# aiie.net
KiCad netlist of a schematic drawn in EAGLE
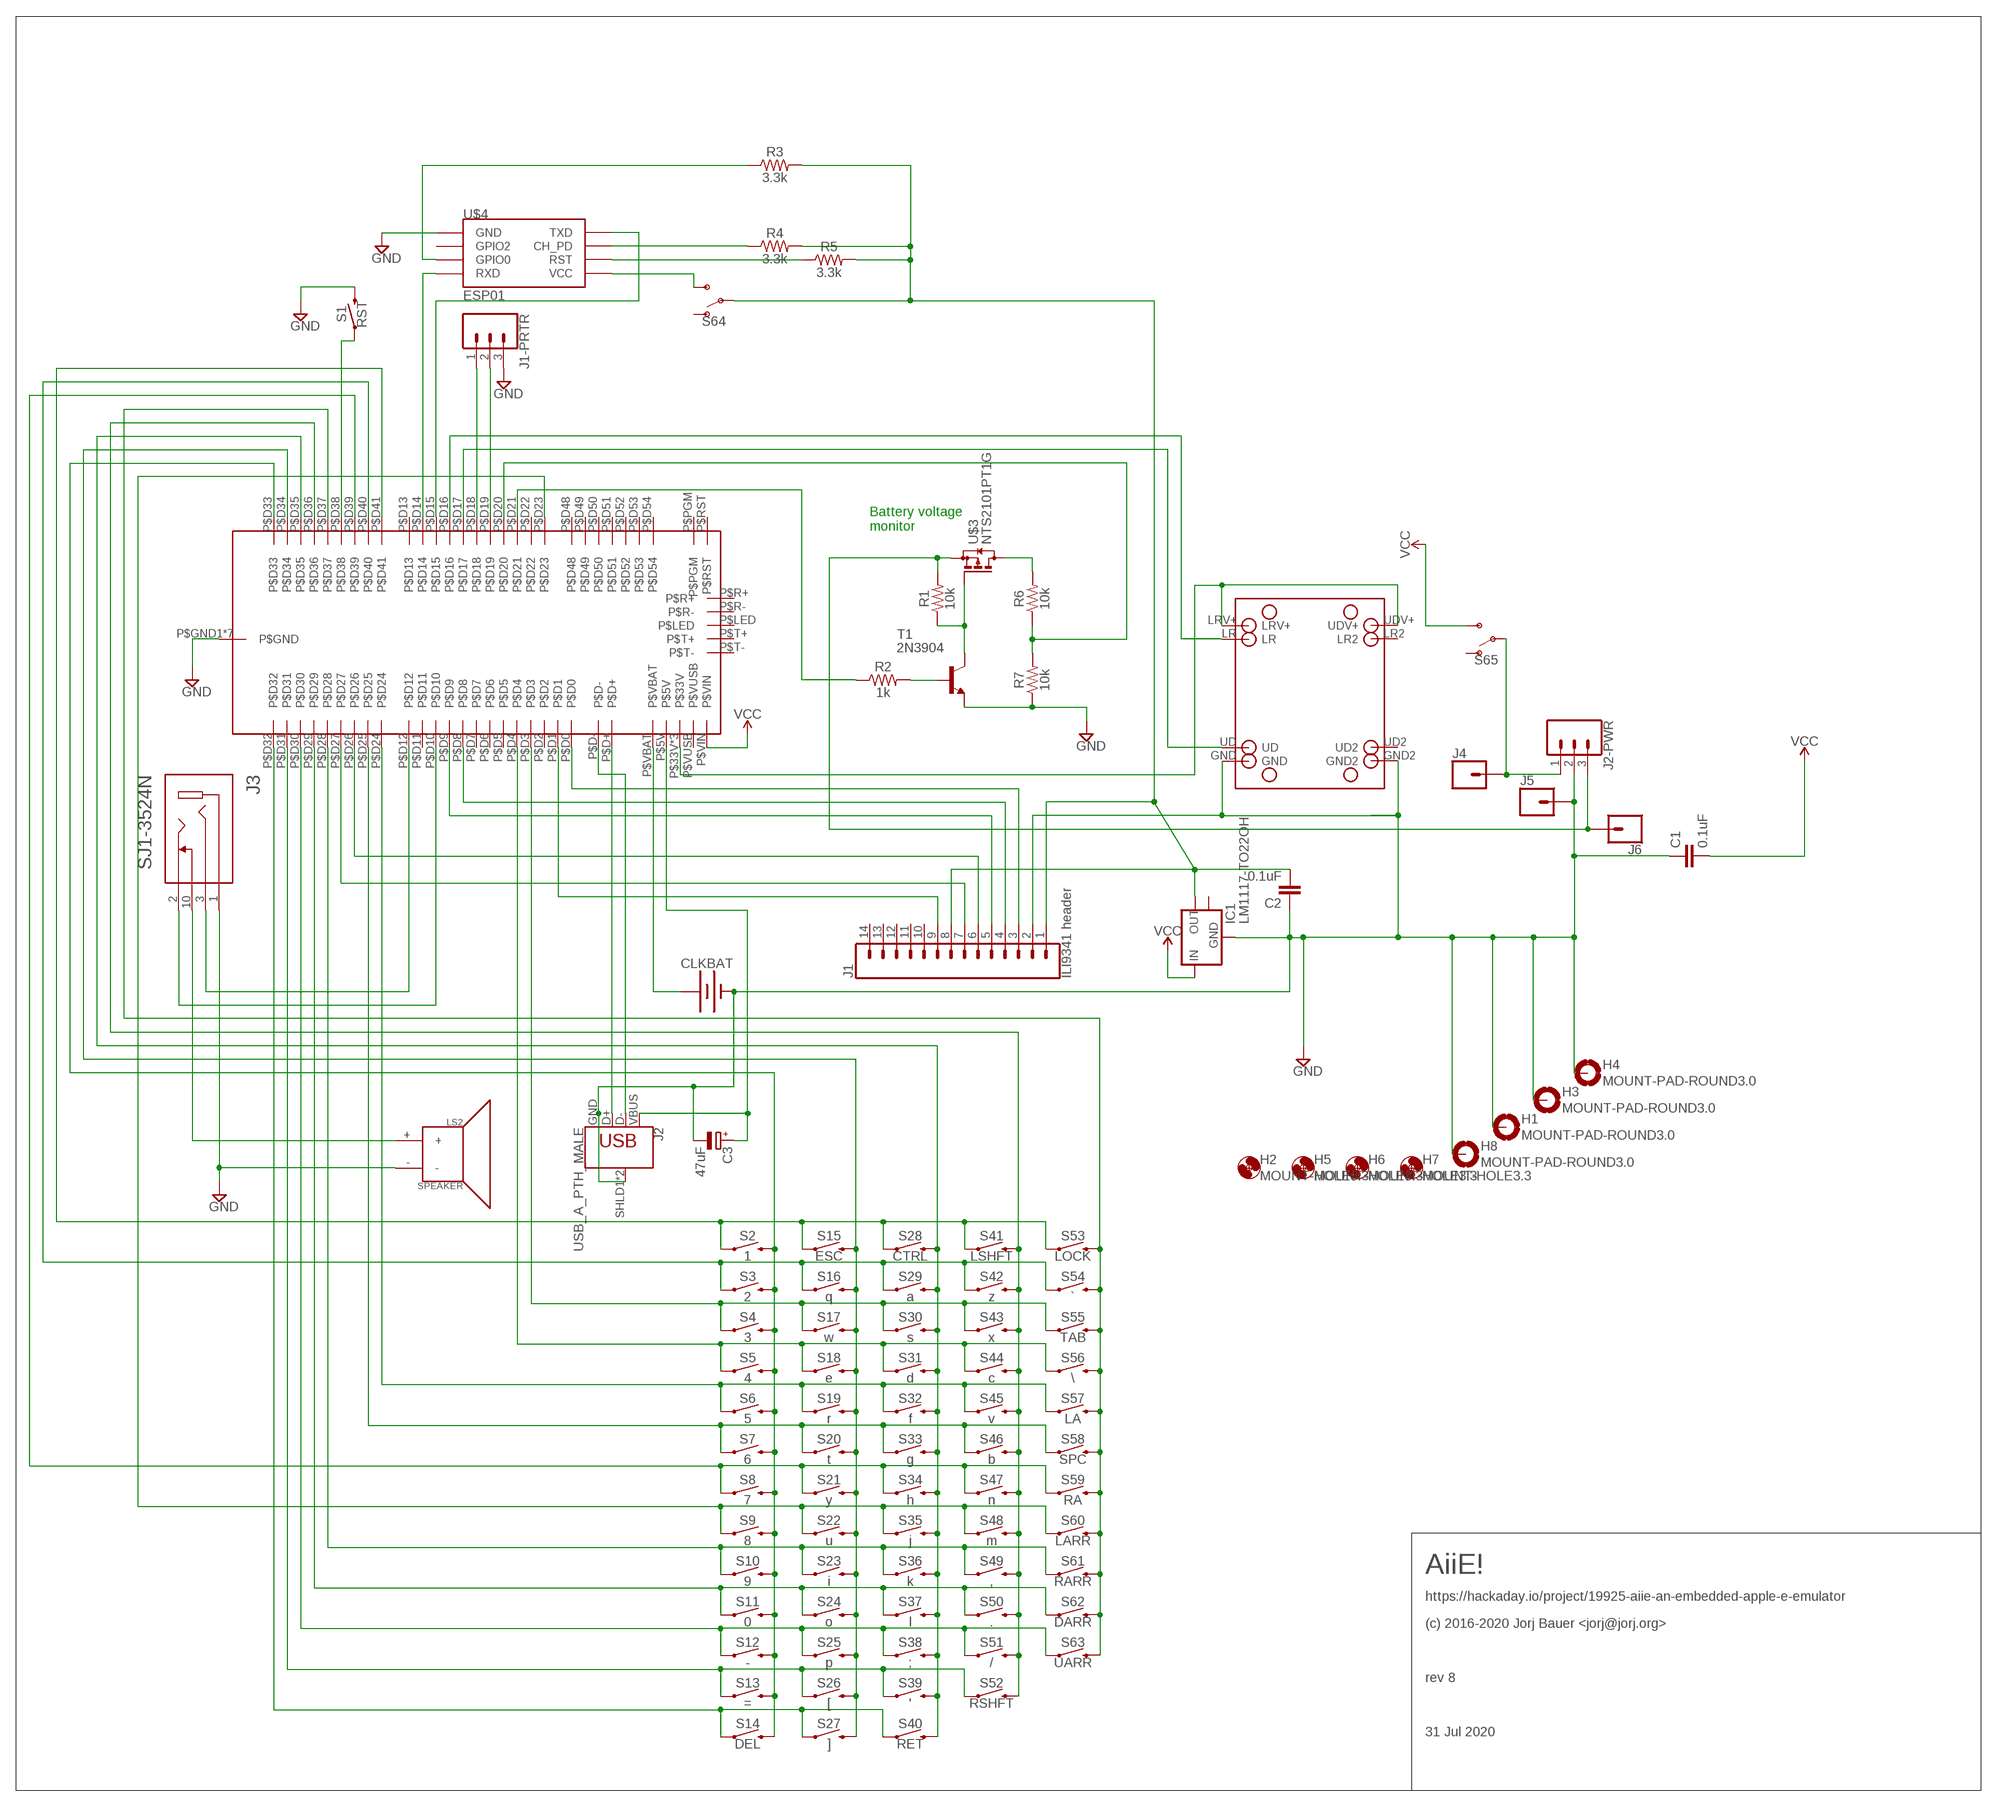
[diagram p0: schematic, sheet 1]

(export (version "E")
  (design (tool "Eeschema 10.0.6"))
  (components
    (comp (ref "C1")
      (value "0.1uF")
      (footprint "eagle-import:C025_050-025X075")
      (libsource (lib "eagle-import") (part "C-EU025_050-025X075"))
    )
    (comp (ref "C2")
      (value "0.1uF")
      (footprint "eagle-import:C025_050-025X075")
      (libsource (lib "eagle-import") (part "C-EU025_050-025X075"))
    )
    (comp (ref "C3")
      (value "47uF")
      (footprint "eagle-import:CAPPRD508W65D1000H1100B")
      (libsource (lib "eagle-import") (part "C-POLRADIAL-11MM-DIA_"))
    )
    (comp (ref "CLKBAT")
      (value "BATTERY-20MM_PTH")
      (footprint "eagle-import:BATTCOM_20MM_PTH")
      (libsource (lib "eagle-import") (part "BATTERY-20MM_PTH"))
    )
    (comp (ref "H1")
      (value "MOUNT-PAD-ROUND3.0")
      (footprint "eagle-import:3,0-PAD")
      (libsource (lib "eagle-import") (part "MOUNT-PAD-ROUND3.0"))
    )
    (comp (ref "H2")
      (value "MOUNT-HOLE3.3")
      (footprint "eagle-import:3,3")
      (libsource (lib "eagle-import") (part "MOUNT-HOLE3.3"))
    )
    (comp (ref "H3")
      (value "MOUNT-PAD-ROUND3.0")
      (footprint "eagle-import:3,0-PAD")
      (libsource (lib "eagle-import") (part "MOUNT-PAD-ROUND3.0"))
    )
    (comp (ref "H4")
      (value "MOUNT-PAD-ROUND3.0")
      (footprint "eagle-import:3,0-PAD")
      (libsource (lib "eagle-import") (part "MOUNT-PAD-ROUND3.0"))
    )
    (comp (ref "H5")
      (value "MOUNT-HOLE3.3")
      (footprint "eagle-import:3,3")
      (libsource (lib "eagle-import") (part "MOUNT-HOLE3.3"))
    )
    (comp (ref "H6")
      (value "MOUNT-HOLE3.3")
      (footprint "eagle-import:3,3")
      (libsource (lib "eagle-import") (part "MOUNT-HOLE3.3"))
    )
    (comp (ref "H7")
      (value "MOUNT-HOLE3.3")
      (footprint "eagle-import:3,3")
      (libsource (lib "eagle-import") (part "MOUNT-HOLE3.3"))
    )
    (comp (ref "H8")
      (value "MOUNT-PAD-ROUND3.0")
      (footprint "eagle-import:3,0-PAD")
      (libsource (lib "eagle-import") (part "MOUNT-PAD-ROUND3.0"))
    )
    (comp (ref "IC1")
      (value "LM1117-TO22OH")
      (footprint "eagle-import:TO220L1")
      (libsource (lib "eagle-import") (part "LM1117-TO22OH"))
    )
    (comp (ref "J1")
      (value "ILI9341 header")
      (footprint "eagle-import:1X14")
      (libsource (lib "eagle-import") (part "CONN_14"))
    )
    (comp (ref "J1-PRTR")
      (value "CONN_03")
      (footprint "eagle-import:1X03")
      (libsource (lib "eagle-import") (part "CONN_03"))
    )
    (comp (ref "J2")
      (value "USB_A_PTH_MALE")
      (footprint "eagle-import:USB-A-H")
      (libsource (lib "eagle-import") (part "USB_A_PTH_MALE"))
    )
    (comp (ref "J2-PWR")
      (value "CONN_03")
      (footprint "eagle-import:1X03")
      (libsource (lib "eagle-import") (part "CONN_03"))
    )
    (comp (ref "J3")
      (value "SJ1-3524N")
      (footprint "eagle-import:CUI_SJ1-3524N")
      (fields (field (name "DIGI-KEY_PART_NUMBER") "CP1-3524NG-ND") (field (name "MF") "CUI Devices"))
      (libsource (lib "eagle-import") (part "SJ1-3524N"))
    )
    (comp (ref "J4")
      (value "CONN_01")
      (footprint "eagle-import:1X01")
      (libsource (lib "eagle-import") (part "CONN_01"))
    )
    (comp (ref "J5")
      (value "CONN_01")
      (footprint "eagle-import:1X01")
      (libsource (lib "eagle-import") (part "CONN_01"))
    )
    (comp (ref "J6")
      (value "CONN_01")
      (footprint "eagle-import:1X01")
      (libsource (lib "eagle-import") (part "CONN_01"))
    )
    (comp (ref "LS2")
      (value "SPEAKER")
      (footprint "eagle-import:PCB_MOUNT_SPEAKER")
      (libsource (lib "eagle-import") (part "SPEAKER"))
    )
    (comp (ref "R1")
      (value "10k")
      (footprint "eagle-import:AXIAL-0.3")
      (libsource (lib "eagle-import") (part "1KOHM-HORIZ-1/4W-1%"))
    )
    (comp (ref "R2")
      (value "1k")
      (footprint "eagle-import:AXIAL-0.3")
      (libsource (lib "eagle-import") (part "1KOHM-HORIZ-1/4W-1%"))
    )
    (comp (ref "R3")
      (value "3.3k")
      (footprint "eagle-import:AXIAL-0.3")
      (libsource (lib "eagle-import") (part "1KOHM-HORIZ-1/4W-1%"))
    )
    (comp (ref "R4")
      (value "3.3k")
      (footprint "eagle-import:AXIAL-0.3")
      (libsource (lib "eagle-import") (part "1KOHM-HORIZ-1/4W-1%"))
    )
    (comp (ref "R5")
      (value "3.3k")
      (footprint "eagle-import:AXIAL-0.3")
      (libsource (lib "eagle-import") (part "1KOHM-HORIZ-1/4W-1%"))
    )
    (comp (ref "R6")
      (value "10k")
      (footprint "eagle-import:AXIAL-0.3")
      (libsource (lib "eagle-import") (part "1KOHM-HORIZ-1/4W-1%"))
    )
    (comp (ref "R7")
      (value "10k")
      (footprint "eagle-import:AXIAL-0.3")
      (libsource (lib "eagle-import") (part "1KOHM-HORIZ-1/4W-1%"))
    )
    (comp (ref "S1")
      (value "RST")
      (footprint "eagle-import:TACTILE_SWITCH_PTH_6.0MM")
      (libsource (lib "eagle-import") (part "MOMENTARY-SWITCH-SPST-PTH-6.0MM"))
    )
    (comp (ref "S2")
      (value "1")
      (footprint "eagle-import:TACTILE_SWITCH_PTH_6.0MM")
      (libsource (lib "eagle-import") (part "MOMENTARY-SWITCH-SPST-PTH-6.0MM"))
    )
    (comp (ref "S3")
      (value "2")
      (footprint "eagle-import:TACTILE_SWITCH_PTH_6.0MM")
      (libsource (lib "eagle-import") (part "MOMENTARY-SWITCH-SPST-PTH-6.0MM"))
    )
    (comp (ref "S4")
      (value "3")
      (footprint "eagle-import:TACTILE_SWITCH_PTH_6.0MM")
      (libsource (lib "eagle-import") (part "MOMENTARY-SWITCH-SPST-PTH-6.0MM"))
    )
    (comp (ref "S5")
      (value "4")
      (footprint "eagle-import:TACTILE_SWITCH_PTH_6.0MM")
      (libsource (lib "eagle-import") (part "MOMENTARY-SWITCH-SPST-PTH-6.0MM"))
    )
    (comp (ref "S6")
      (value "5")
      (footprint "eagle-import:TACTILE_SWITCH_PTH_6.0MM")
      (libsource (lib "eagle-import") (part "MOMENTARY-SWITCH-SPST-PTH-6.0MM"))
    )
    (comp (ref "S7")
      (value "6")
      (footprint "eagle-import:TACTILE_SWITCH_PTH_6.0MM")
      (libsource (lib "eagle-import") (part "MOMENTARY-SWITCH-SPST-PTH-6.0MM"))
    )
    (comp (ref "S8")
      (value "7")
      (footprint "eagle-import:TACTILE_SWITCH_PTH_6.0MM")
      (libsource (lib "eagle-import") (part "MOMENTARY-SWITCH-SPST-PTH-6.0MM"))
    )
    (comp (ref "S9")
      (value "8")
      (footprint "eagle-import:TACTILE_SWITCH_PTH_6.0MM")
      (libsource (lib "eagle-import") (part "MOMENTARY-SWITCH-SPST-PTH-6.0MM"))
    )
    (comp (ref "S10")
      (value "9")
      (footprint "eagle-import:TACTILE_SWITCH_PTH_6.0MM")
      (libsource (lib "eagle-import") (part "MOMENTARY-SWITCH-SPST-PTH-6.0MM"))
    )
    (comp (ref "S11")
      (value "0")
      (footprint "eagle-import:TACTILE_SWITCH_PTH_6.0MM")
      (libsource (lib "eagle-import") (part "MOMENTARY-SWITCH-SPST-PTH-6.0MM"))
    )
    (comp (ref "S12")
      (value "-")
      (footprint "eagle-import:TACTILE_SWITCH_PTH_6.0MM")
      (libsource (lib "eagle-import") (part "MOMENTARY-SWITCH-SPST-PTH-6.0MM"))
    )
    (comp (ref "S13")
      (value "=")
      (footprint "eagle-import:TACTILE_SWITCH_PTH_6.0MM")
      (libsource (lib "eagle-import") (part "MOMENTARY-SWITCH-SPST-PTH-6.0MM"))
    )
    (comp (ref "S14")
      (value "DEL")
      (footprint "eagle-import:TACTILE_SWITCH_PTH_6.0MM")
      (libsource (lib "eagle-import") (part "MOMENTARY-SWITCH-SPST-PTH-6.0MM"))
    )
    (comp (ref "S15")
      (value "ESC")
      (footprint "eagle-import:TACTILE_SWITCH_PTH_6.0MM")
      (libsource (lib "eagle-import") (part "MOMENTARY-SWITCH-SPST-PTH-6.0MM"))
    )
    (comp (ref "S16")
      (value "q")
      (footprint "eagle-import:TACTILE_SWITCH_PTH_6.0MM")
      (libsource (lib "eagle-import") (part "MOMENTARY-SWITCH-SPST-PTH-6.0MM"))
    )
    (comp (ref "S17")
      (value "w")
      (footprint "eagle-import:TACTILE_SWITCH_PTH_6.0MM")
      (libsource (lib "eagle-import") (part "MOMENTARY-SWITCH-SPST-PTH-6.0MM"))
    )
    (comp (ref "S18")
      (value "e")
      (footprint "eagle-import:TACTILE_SWITCH_PTH_6.0MM")
      (libsource (lib "eagle-import") (part "MOMENTARY-SWITCH-SPST-PTH-6.0MM"))
    )
    (comp (ref "S19")
      (value "r")
      (footprint "eagle-import:TACTILE_SWITCH_PTH_6.0MM")
      (libsource (lib "eagle-import") (part "MOMENTARY-SWITCH-SPST-PTH-6.0MM"))
    )
    (comp (ref "S20")
      (value "t")
      (footprint "eagle-import:TACTILE_SWITCH_PTH_6.0MM")
      (libsource (lib "eagle-import") (part "MOMENTARY-SWITCH-SPST-PTH-6.0MM"))
    )
    (comp (ref "S21")
      (value "y")
      (footprint "eagle-import:TACTILE_SWITCH_PTH_6.0MM")
      (libsource (lib "eagle-import") (part "MOMENTARY-SWITCH-SPST-PTH-6.0MM"))
    )
    (comp (ref "S22")
      (value "u")
      (footprint "eagle-import:TACTILE_SWITCH_PTH_6.0MM")
      (libsource (lib "eagle-import") (part "MOMENTARY-SWITCH-SPST-PTH-6.0MM"))
    )
    (comp (ref "S23")
      (value "i")
      (footprint "eagle-import:TACTILE_SWITCH_PTH_6.0MM")
      (libsource (lib "eagle-import") (part "MOMENTARY-SWITCH-SPST-PTH-6.0MM"))
    )
    (comp (ref "S24")
      (value "o")
      (footprint "eagle-import:TACTILE_SWITCH_PTH_6.0MM")
      (libsource (lib "eagle-import") (part "MOMENTARY-SWITCH-SPST-PTH-6.0MM"))
    )
    (comp (ref "S25")
      (value "p")
      (footprint "eagle-import:TACTILE_SWITCH_PTH_6.0MM")
      (libsource (lib "eagle-import") (part "MOMENTARY-SWITCH-SPST-PTH-6.0MM"))
    )
    (comp (ref "S26")
      (value "[")
      (footprint "eagle-import:TACTILE_SWITCH_PTH_6.0MM")
      (libsource (lib "eagle-import") (part "MOMENTARY-SWITCH-SPST-PTH-6.0MM"))
    )
    (comp (ref "S27")
      (value "]")
      (footprint "eagle-import:TACTILE_SWITCH_PTH_6.0MM")
      (libsource (lib "eagle-import") (part "MOMENTARY-SWITCH-SPST-PTH-6.0MM"))
    )
    (comp (ref "S28")
      (value "CTRL")
      (footprint "eagle-import:TACTILE_SWITCH_PTH_6.0MM")
      (libsource (lib "eagle-import") (part "MOMENTARY-SWITCH-SPST-PTH-6.0MM"))
    )
    (comp (ref "S29")
      (value "a")
      (footprint "eagle-import:TACTILE_SWITCH_PTH_6.0MM")
      (libsource (lib "eagle-import") (part "MOMENTARY-SWITCH-SPST-PTH-6.0MM"))
    )
    (comp (ref "S30")
      (value "s")
      (footprint "eagle-import:TACTILE_SWITCH_PTH_6.0MM")
      (libsource (lib "eagle-import") (part "MOMENTARY-SWITCH-SPST-PTH-6.0MM"))
    )
    (comp (ref "S31")
      (value "d")
      (footprint "eagle-import:TACTILE_SWITCH_PTH_6.0MM")
      (libsource (lib "eagle-import") (part "MOMENTARY-SWITCH-SPST-PTH-6.0MM"))
    )
    (comp (ref "S32")
      (value "f")
      (footprint "eagle-import:TACTILE_SWITCH_PTH_6.0MM")
      (libsource (lib "eagle-import") (part "MOMENTARY-SWITCH-SPST-PTH-6.0MM"))
    )
    (comp (ref "S33")
      (value "g")
      (footprint "eagle-import:TACTILE_SWITCH_PTH_6.0MM")
      (libsource (lib "eagle-import") (part "MOMENTARY-SWITCH-SPST-PTH-6.0MM"))
    )
    (comp (ref "S34")
      (value "h")
      (footprint "eagle-import:TACTILE_SWITCH_PTH_6.0MM")
      (libsource (lib "eagle-import") (part "MOMENTARY-SWITCH-SPST-PTH-6.0MM"))
    )
    (comp (ref "S35")
      (value "j")
      (footprint "eagle-import:TACTILE_SWITCH_PTH_6.0MM")
      (libsource (lib "eagle-import") (part "MOMENTARY-SWITCH-SPST-PTH-6.0MM"))
    )
    (comp (ref "S36")
      (value "k")
      (footprint "eagle-import:TACTILE_SWITCH_PTH_6.0MM")
      (libsource (lib "eagle-import") (part "MOMENTARY-SWITCH-SPST-PTH-6.0MM"))
    )
    (comp (ref "S37")
      (value "l")
      (footprint "eagle-import:TACTILE_SWITCH_PTH_6.0MM")
      (libsource (lib "eagle-import") (part "MOMENTARY-SWITCH-SPST-PTH-6.0MM"))
    )
    (comp (ref "S38")
      (value ";")
      (footprint "eagle-import:TACTILE_SWITCH_PTH_6.0MM")
      (libsource (lib "eagle-import") (part "MOMENTARY-SWITCH-SPST-PTH-6.0MM"))
    )
    (comp (ref "S39")
      (value "'")
      (footprint "eagle-import:TACTILE_SWITCH_PTH_6.0MM")
      (libsource (lib "eagle-import") (part "MOMENTARY-SWITCH-SPST-PTH-6.0MM"))
    )
    (comp (ref "S40")
      (value "RET")
      (footprint "eagle-import:TACTILE_SWITCH_PTH_6.0MM")
      (libsource (lib "eagle-import") (part "MOMENTARY-SWITCH-SPST-PTH-6.0MM"))
    )
    (comp (ref "S41")
      (value "LSHFT")
      (footprint "eagle-import:TACTILE_SWITCH_PTH_6.0MM")
      (libsource (lib "eagle-import") (part "MOMENTARY-SWITCH-SPST-PTH-6.0MM"))
    )
    (comp (ref "S42")
      (value "z")
      (footprint "eagle-import:TACTILE_SWITCH_PTH_6.0MM")
      (libsource (lib "eagle-import") (part "MOMENTARY-SWITCH-SPST-PTH-6.0MM"))
    )
    (comp (ref "S43")
      (value "x")
      (footprint "eagle-import:TACTILE_SWITCH_PTH_6.0MM")
      (libsource (lib "eagle-import") (part "MOMENTARY-SWITCH-SPST-PTH-6.0MM"))
    )
    (comp (ref "S44")
      (value "c")
      (footprint "eagle-import:TACTILE_SWITCH_PTH_6.0MM")
      (libsource (lib "eagle-import") (part "MOMENTARY-SWITCH-SPST-PTH-6.0MM"))
    )
    (comp (ref "S45")
      (value "v")
      (footprint "eagle-import:TACTILE_SWITCH_PTH_6.0MM")
      (libsource (lib "eagle-import") (part "MOMENTARY-SWITCH-SPST-PTH-6.0MM"))
    )
    (comp (ref "S46")
      (value "b")
      (footprint "eagle-import:TACTILE_SWITCH_PTH_6.0MM")
      (libsource (lib "eagle-import") (part "MOMENTARY-SWITCH-SPST-PTH-6.0MM"))
    )
    (comp (ref "S47")
      (value "n")
      (footprint "eagle-import:TACTILE_SWITCH_PTH_6.0MM")
      (libsource (lib "eagle-import") (part "MOMENTARY-SWITCH-SPST-PTH-6.0MM"))
    )
    (comp (ref "S48")
      (value "m")
      (footprint "eagle-import:TACTILE_SWITCH_PTH_6.0MM")
      (libsource (lib "eagle-import") (part "MOMENTARY-SWITCH-SPST-PTH-6.0MM"))
    )
    (comp (ref "S49")
      (value ",")
      (footprint "eagle-import:TACTILE_SWITCH_PTH_6.0MM")
      (libsource (lib "eagle-import") (part "MOMENTARY-SWITCH-SPST-PTH-6.0MM"))
    )
    (comp (ref "S50")
      (value ".")
      (footprint "eagle-import:TACTILE_SWITCH_PTH_6.0MM")
      (libsource (lib "eagle-import") (part "MOMENTARY-SWITCH-SPST-PTH-6.0MM"))
    )
    (comp (ref "S51")
      (value "/")
      (footprint "eagle-import:TACTILE_SWITCH_PTH_6.0MM")
      (libsource (lib "eagle-import") (part "MOMENTARY-SWITCH-SPST-PTH-6.0MM"))
    )
    (comp (ref "S52")
      (value "RSHFT")
      (footprint "eagle-import:TACTILE_SWITCH_PTH_6.0MM")
      (libsource (lib "eagle-import") (part "MOMENTARY-SWITCH-SPST-PTH-6.0MM"))
    )
    (comp (ref "S53")
      (value "LOCK")
      (footprint "eagle-import:TACTILE_SWITCH_PTH_6.0MM")
      (libsource (lib "eagle-import") (part "MOMENTARY-SWITCH-SPST-PTH-6.0MM"))
    )
    (comp (ref "S54")
      (value "`")
      (footprint "eagle-import:TACTILE_SWITCH_PTH_6.0MM")
      (libsource (lib "eagle-import") (part "MOMENTARY-SWITCH-SPST-PTH-6.0MM"))
    )
    (comp (ref "S55")
      (value "TAB")
      (footprint "eagle-import:TACTILE_SWITCH_PTH_6.0MM")
      (libsource (lib "eagle-import") (part "MOMENTARY-SWITCH-SPST-PTH-6.0MM"))
    )
    (comp (ref "S56")
      (value "\\\\")
      (footprint "eagle-import:TACTILE_SWITCH_PTH_6.0MM")
      (libsource (lib "eagle-import") (part "MOMENTARY-SWITCH-SPST-PTH-6.0MM"))
    )
    (comp (ref "S57")
      (value "LA")
      (footprint "eagle-import:TACTILE_SWITCH_PTH_6.0MM")
      (libsource (lib "eagle-import") (part "MOMENTARY-SWITCH-SPST-PTH-6.0MM"))
    )
    (comp (ref "S58")
      (value "SPC")
      (footprint "eagle-import:TACTILE_SWITCH_PTH_6.0MM")
      (libsource (lib "eagle-import") (part "MOMENTARY-SWITCH-SPST-PTH-6.0MM"))
    )
    (comp (ref "S59")
      (value "RA")
      (footprint "eagle-import:TACTILE_SWITCH_PTH_6.0MM")
      (libsource (lib "eagle-import") (part "MOMENTARY-SWITCH-SPST-PTH-6.0MM"))
    )
    (comp (ref "S60")
      (value "LARR")
      (footprint "eagle-import:TACTILE_SWITCH_PTH_6.0MM")
      (libsource (lib "eagle-import") (part "MOMENTARY-SWITCH-SPST-PTH-6.0MM"))
    )
    (comp (ref "S61")
      (value "RARR")
      (footprint "eagle-import:TACTILE_SWITCH_PTH_6.0MM")
      (libsource (lib "eagle-import") (part "MOMENTARY-SWITCH-SPST-PTH-6.0MM"))
    )
    (comp (ref "S62")
      (value "DARR")
      (footprint "eagle-import:TACTILE_SWITCH_PTH_6.0MM")
      (libsource (lib "eagle-import") (part "MOMENTARY-SWITCH-SPST-PTH-6.0MM"))
    )
    (comp (ref "S63")
      (value "UARR")
      (footprint "eagle-import:TACTILE_SWITCH_PTH_6.0MM")
      (libsource (lib "eagle-import") (part "MOMENTARY-SWITCH-SPST-PTH-6.0MM"))
    )
    (comp (ref "S64")
      (value "SWITCH-SPDT-PTH-11.6X4.0MM")
      (footprint "eagle-import:SWITCH_SPDT_PTH_11.6X4.0MM")
      (libsource (lib "eagle-import") (part "SWITCH-SPDT-PTH-11.6X4.0MM"))
    )
    (comp (ref "S65")
      (value "SWITCH-SPDT-PTH-11.6X4.0MM")
      (footprint "eagle-import:SWITCH_SPDT_PTH_11.6X4.0MM")
      (libsource (lib "eagle-import") (part "SWITCH-SPDT-PTH-11.6X4.0MM"))
    )
    (comp (ref "T1")
      (value "2N3904")
      (footprint "eagle-import:TO92")
      (libsource (lib "eagle-import") (part "2N3904"))
    )
    (comp (ref "U$1")
      (value "PARALLAX2AXIS")
      (footprint "eagle-import:PARALLAX2AXIS")
      (libsource (lib "eagle-import") (part "PARALLAX2AXIS"))
    )
    (comp (ref "U$2")
      (value "TEENSY41")
      (footprint "eagle-import:TEENSY41")
      (libsource (lib "eagle-import") (part "TEENSY41"))
    )
    (comp (ref "U$3")
      (value "NTS2101PT1G")
      (footprint "eagle-import:SOT323")
      (fields
        (field (name "DIGI-KEY_PART_NUMBER") "NTS2101PT1GOSCT-ND")
        (field (name "MF") "ON Semiconductor")
      )
      (libsource (lib "eagle-import") (part "NTS2101PT1G"))
    )
    (comp (ref "U$4")
      (value "ESP01")
      (footprint "eagle-import:ESP01")
      (libsource (lib "eagle-import") (part "ESP01"))
    )
  )
  (nets
    (net (code "1") (name "GND") (class "Default")
      (node (ref "C1") (pin "1") (pinfunction "1_1") (pintype "passive"))
      (node (ref "C2") (pin "1") (pinfunction "1_1") (pintype "passive"))
      (node (ref "C3") (pin "2") (pinfunction "-_2") (pintype "passive"))
      (node (ref "CLKBAT") (pin "2") (pinfunction "-_2") (pintype "power_in"))
      (node (ref "H1") (pin "B3,0") (pinfunction "MOUNT_B3,0") (pintype "passive"))
      (node (ref "H3") (pin "B3,0") (pinfunction "MOUNT_B3,0") (pintype "passive"))
      (node (ref "H4") (pin "B3,0") (pinfunction "MOUNT_B3,0") (pintype "passive"))
      (node (ref "H8") (pin "B3,0") (pinfunction "MOUNT_B3,0") (pintype "passive"))
      (node (ref "IC1") (pin "1") (pinfunction "GND_1") (pintype "bidirectional"))
      (node (ref "J1") (pin "2") (pinfunction "2_2") (pintype "passive"))
      (node (ref "J1-PRTR") (pin "3") (pinfunction "3_3") (pintype "passive"))
      (node (ref "J2") (pin "GND") (pinfunction "GND_GND") (pintype "power_in"))
      (node (ref "J2") (pin "SHLD1") (pinfunction "SHIELD_SHLD1") (pintype "bidirectional"))
      (node (ref "J2") (pin "SHLD2") (pinfunction "SHIELD_SHLD2") (pintype "bidirectional"))
      (node (ref "J2-PWR") (pin "2") (pinfunction "2_2") (pintype "passive"))
      (node (ref "J3") (pin "1") (pinfunction "1_1") (pintype "passive"))
      (node (ref "J5") (pin "1") (pinfunction "1_1") (pintype "passive"))
      (node (ref "LS2") (pin "-") (pinfunction "-_-") (pintype "bidirectional"))
      (node (ref "R7") (pin "P$1") (pinfunction "1_P$1") (pintype "passive"))
      (node (ref "S1") (pin "3") (pinfunction "2_3") (pintype "passive"))
      (node (ref "T1") (pin "3") (pinfunction "E_3") (pintype "passive"))
      (node (ref "U$1") (pin "GND") (pinfunction "GND_GND") (pintype "bidirectional"))
      (node (ref "U$1") (pin "GND2") (pinfunction "GND2_GND2") (pintype "bidirectional"))
      (node (ref "U$2") (pin "P$GND1") (pinfunction "P$GND_P$GND1") (pintype "bidirectional"))
      (node (ref "U$2") (pin "P$GND2") (pinfunction "P$GND_P$GND2") (pintype "bidirectional"))
      (node (ref "U$2") (pin "P$GND3") (pinfunction "P$GND_P$GND3") (pintype "bidirectional"))
      (node (ref "U$2") (pin "P$GND4") (pinfunction "P$GND_P$GND4") (pintype "bidirectional"))
      (node (ref "U$2") (pin "P$GND5") (pinfunction "P$GND_P$GND5") (pintype "bidirectional"))
      (node (ref "U$2") (pin "P$GND6") (pinfunction "P$GND_P$GND6") (pintype "bidirectional"))
      (node (ref "U$2") (pin "P$GND7") (pinfunction "P$GND_P$GND7") (pintype "bidirectional"))
      (node (ref "U$4") (pin "GND") (pinfunction "GND_GND") (pintype "bidirectional"))
    )
    (net (code "2") (name "Net-(C3-+)") (class "Default")
      (node (ref "C3") (pin "1") (pinfunction "+_1") (pintype "passive"))
      (node (ref "J2") (pin "VBUS") (pinfunction "VBUS_VBUS") (pintype "power_in"))
      (node (ref "U$2") (pin "P$5V") (pinfunction "P$5V_P$5V") (pintype "bidirectional"))
    )
    (net (code "3") (name "Net-(CLKBAT-+)") (class "Default")
      (node (ref "CLKBAT") (pin "1") (pinfunction "+_1") (pintype "power_in"))
      (node (ref "U$2") (pin "P$VBAT") (pinfunction "P$VBAT_P$VBAT") (pintype "bidirectional"))
    )
    (net (code "4") (name "Net-(IC1-VOUT)") (class "Default")
      (node (ref "C2") (pin "2") (pinfunction "2_2") (pintype "passive"))
      (node (ref "IC1") (pin "2") (pinfunction "VOUT_2") (pintype "bidirectional"))
      (node (ref "J1") (pin "1") (pinfunction "1_1") (pintype "passive"))
      (node (ref "J1") (pin "8") (pinfunction "8_8") (pintype "passive"))
      (node (ref "R3") (pin "P$2") (pinfunction "2_P$2") (pintype "passive"))
      (node (ref "R4") (pin "P$2") (pinfunction "2_P$2") (pintype "passive"))
      (node (ref "R5") (pin "P$2") (pinfunction "2_P$2") (pintype "passive"))
      (node (ref "S64") (pin "2") (pinfunction "P_2") (pintype "passive"))
    )
    (net (code "5") (name "Net-(J1-PRTR-Pad1)") (class "Default")
      (node (ref "J1-PRTR") (pin "1") (pinfunction "1_1") (pintype "passive"))
      (node (ref "U$2") (pin "P$D18") (pinfunction "P$D18_P$D18") (pintype "bidirectional"))
    )
    (net (code "6") (name "Net-(J1-PRTR-Pad2)") (class "Default")
      (node (ref "J1-PRTR") (pin "2") (pinfunction "2_2") (pintype "passive"))
      (node (ref "U$2") (pin "P$D19") (pinfunction "P$D19_P$D19") (pintype "bidirectional"))
    )
    (net (code "7") (name "Net-(J1-Pad3)") (class "Default")
      (node (ref "J1") (pin "3") (pinfunction "3_3") (pintype "passive"))
      (node (ref "U$2") (pin "P$D0") (pinfunction "P$D0_P$D0") (pintype "bidirectional"))
    )
    (net (code "8") (name "Net-(J1-Pad4)") (class "Default")
      (node (ref "J1") (pin "4") (pinfunction "4_4") (pintype "passive"))
      (node (ref "U$2") (pin "P$D8") (pinfunction "P$D8_P$D8") (pintype "bidirectional"))
    )
    (net (code "9") (name "Net-(J1-Pad5)") (class "Default")
      (node (ref "J1") (pin "5") (pinfunction "5_5") (pintype "passive"))
      (node (ref "U$2") (pin "P$D9") (pinfunction "P$D9_P$D9") (pintype "bidirectional"))
    )
    (net (code "10") (name "Net-(J1-Pad6)") (class "Default")
      (node (ref "J1") (pin "6") (pinfunction "6_6") (pintype "passive"))
      (node (ref "U$2") (pin "P$D26") (pinfunction "P$D26_P$D26") (pintype "bidirectional"))
    )
    (net (code "11") (name "Net-(J1-Pad7)") (class "Default")
      (node (ref "J1") (pin "7") (pinfunction "7_7") (pintype "passive"))
      (node (ref "U$2") (pin "P$D27") (pinfunction "P$D27_P$D27") (pintype "bidirectional"))
    )
    (net (code "12") (name "Net-(J1-Pad9)") (class "Default")
      (node (ref "J1") (pin "9") (pinfunction "9_9") (pintype "passive"))
      (node (ref "U$2") (pin "P$D1") (pinfunction "P$D1_P$D1") (pintype "bidirectional"))
    )
    (net (code "13") (name "Net-(J2-PadD+)") (class "Default")
      (node (ref "J2") (pin "D+") (pinfunction "D+_D+") (pintype "bidirectional"))
      (node (ref "U$2") (pin "P$D+") (pinfunction "P$D+_P$D+") (pintype "bidirectional"))
    )
    (net (code "14") (name "Net-(J2-PadD-)") (class "Default")
      (node (ref "J2") (pin "D-") (pinfunction "D-_D-") (pintype "bidirectional"))
      (node (ref "U$2") (pin "P$D-") (pinfunction "P$D-_P$D-") (pintype "bidirectional"))
    )
    (net (code "15") (name "Net-(J3-Pad2)") (class "Default")
      (node (ref "J3") (pin "2") (pinfunction "2_2") (pintype "passive"))
      (node (ref "U$2") (pin "P$D10") (pinfunction "P$D10_P$D10") (pintype "bidirectional"))
    )
    (net (code "16") (name "Net-(J3-Pad3)") (class "Default")
      (node (ref "J3") (pin "3") (pinfunction "3_3") (pintype "passive"))
      (node (ref "U$2") (pin "P$D12") (pinfunction "P$D12_P$D12") (pintype "bidirectional"))
    )
    (net (code "17") (name "Net-(J3-Pad10)") (class "Default")
      (node (ref "J3") (pin "10") (pinfunction "10_10") (pintype "passive"))
      (node (ref "LS2") (pin "+") (pinfunction "+_+") (pintype "bidirectional"))
    )
    (net (code "18") (name "Net-(R1-1)") (class "Default")
      (node (ref "R1") (pin "P$1") (pinfunction "1_P$1") (pintype "passive"))
      (node (ref "T1") (pin "1") (pinfunction "C_1") (pintype "passive"))
      (node (ref "U$3") (pin "1") (pinfunction "G_1") (pintype "passive"))
    )
    (net (code "19") (name "Net-(R1-2)") (class "Default")
      (node (ref "J2-PWR") (pin "3") (pinfunction "3_3") (pintype "passive"))
      (node (ref "J6") (pin "1") (pinfunction "1_1") (pintype "passive"))
      (node (ref "R1") (pin "P$2") (pinfunction "2_P$2") (pintype "passive"))
      (node (ref "U$3") (pin "2") (pinfunction "S_2") (pintype "passive"))
    )
    (net (code "20") (name "Net-(R2-1)") (class "Default")
      (node (ref "R2") (pin "P$1") (pinfunction "1_P$1") (pintype "passive"))
      (node (ref "U$2") (pin "P$D21") (pinfunction "P$D21_P$D21") (pintype "bidirectional"))
    )
    (net (code "21") (name "Net-(R2-2)") (class "Default")
      (node (ref "R2") (pin "P$2") (pinfunction "2_P$2") (pintype "passive"))
      (node (ref "T1") (pin "2") (pinfunction "B_2") (pintype "passive"))
    )
    (net (code "22") (name "Net-(R3-1)") (class "Default")
      (node (ref "R3") (pin "P$1") (pinfunction "1_P$1") (pintype "passive"))
      (node (ref "U$4") (pin "GPIO0") (pinfunction "GPIO0_GPIO0") (pintype "bidirectional"))
    )
    (net (code "23") (name "Net-(R4-1)") (class "Default")
      (node (ref "R4") (pin "P$1") (pinfunction "1_P$1") (pintype "passive"))
      (node (ref "U$4") (pin "CH_PD") (pinfunction "CH_PD_CH_PD") (pintype "bidirectional"))
    )
    (net (code "24") (name "Net-(R5-1)") (class "Default")
      (node (ref "R5") (pin "P$1") (pinfunction "1_P$1") (pintype "passive"))
      (node (ref "U$4") (pin "RST") (pinfunction "RST_RST") (pintype "bidirectional"))
    )
    (net (code "25") (name "Net-(R6-1)") (class "Default")
      (node (ref "R6") (pin "P$1") (pinfunction "1_P$1") (pintype "passive"))
      (node (ref "R7") (pin "P$2") (pinfunction "2_P$2") (pintype "passive"))
      (node (ref "U$2") (pin "P$D20") (pinfunction "P$D20_P$D20") (pintype "bidirectional"))
    )
    (net (code "26") (name "Net-(R6-2)") (class "Default")
      (node (ref "R6") (pin "P$2") (pinfunction "2_P$2") (pintype "passive"))
      (node (ref "U$3") (pin "3") (pinfunction "D_3") (pintype "passive"))
    )
    (net (code "27") (name "Net-(S1-Pad1)") (class "Default")
      (node (ref "S1") (pin "1") (pinfunction "1_1") (pintype "passive"))
      (node (ref "U$2") (pin "P$D38") (pinfunction "P$D38_P$D38") (pintype "bidirectional"))
    )
    (net (code "28") (name "Net-(S10-2)") (class "Default")
      (node (ref "S10") (pin "3") (pinfunction "2_3") (pintype "passive"))
      (node (ref "S11") (pin "3") (pinfunction "2_3") (pintype "passive"))
      (node (ref "S12") (pin "3") (pinfunction "2_3") (pintype "passive"))
      (node (ref "S13") (pin "3") (pinfunction "2_3") (pintype "passive"))
      (node (ref "S14") (pin "3") (pinfunction "2_3") (pintype "passive"))
      (node (ref "S2") (pin "3") (pinfunction "2_3") (pintype "passive"))
      (node (ref "S3") (pin "3") (pinfunction "2_3") (pintype "passive"))
      (node (ref "S4") (pin "3") (pinfunction "2_3") (pintype "passive"))
      (node (ref "S5") (pin "3") (pinfunction "2_3") (pintype "passive"))
      (node (ref "S6") (pin "3") (pinfunction "2_3") (pintype "passive"))
      (node (ref "S7") (pin "3") (pinfunction "2_3") (pintype "passive"))
      (node (ref "S8") (pin "3") (pinfunction "2_3") (pintype "passive"))
      (node (ref "S9") (pin "3") (pinfunction "2_3") (pintype "passive"))
      (node (ref "U$2") (pin "P$D33") (pinfunction "P$D33_P$D33") (pintype "bidirectional"))
    )
    (net (code "29") (name "Net-(S10-Pad1)") (class "Default")
      (node (ref "S10") (pin "1") (pinfunction "1_1") (pintype "passive"))
      (node (ref "S23") (pin "1") (pinfunction "1_1") (pintype "passive"))
      (node (ref "S36") (pin "1") (pinfunction "1_1") (pintype "passive"))
      (node (ref "S49") (pin "1") (pinfunction "1_1") (pintype "passive"))
      (node (ref "S61") (pin "1") (pinfunction "1_1") (pintype "passive"))
      (node (ref "U$2") (pin "P$D28") (pinfunction "P$D28_P$D28") (pintype "bidirectional"))
    )
    (net (code "30") (name "Net-(S11-Pad1)") (class "Default")
      (node (ref "S11") (pin "1") (pinfunction "1_1") (pintype "passive"))
      (node (ref "S24") (pin "1") (pinfunction "1_1") (pintype "passive"))
      (node (ref "S37") (pin "1") (pinfunction "1_1") (pintype "passive"))
      (node (ref "S50") (pin "1") (pinfunction "1_1") (pintype "passive"))
      (node (ref "S62") (pin "1") (pinfunction "1_1") (pintype "passive"))
      (node (ref "U$2") (pin "P$D29") (pinfunction "P$D29_P$D29") (pintype "bidirectional"))
    )
    (net (code "31") (name "Net-(S12-Pad1)") (class "Default")
      (node (ref "S12") (pin "1") (pinfunction "1_1") (pintype "passive"))
      (node (ref "S25") (pin "1") (pinfunction "1_1") (pintype "passive"))
      (node (ref "S38") (pin "1") (pinfunction "1_1") (pintype "passive"))
      (node (ref "S51") (pin "1") (pinfunction "1_1") (pintype "passive"))
      (node (ref "S63") (pin "1") (pinfunction "1_1") (pintype "passive"))
      (node (ref "U$2") (pin "P$D30") (pinfunction "P$D30_P$D30") (pintype "bidirectional"))
    )
    (net (code "32") (name "Net-(S13-Pad1)") (class "Default")
      (node (ref "S13") (pin "1") (pinfunction "1_1") (pintype "passive"))
      (node (ref "S26") (pin "1") (pinfunction "1_1") (pintype "passive"))
      (node (ref "S39") (pin "1") (pinfunction "1_1") (pintype "passive"))
      (node (ref "S52") (pin "1") (pinfunction "1_1") (pintype "passive"))
      (node (ref "U$2") (pin "P$D31") (pinfunction "P$D31_P$D31") (pintype "bidirectional"))
    )
    (net (code "33") (name "Net-(S14-Pad1)") (class "Default")
      (node (ref "S14") (pin "1") (pinfunction "1_1") (pintype "passive"))
      (node (ref "S27") (pin "1") (pinfunction "1_1") (pintype "passive"))
      (node (ref "S40") (pin "1") (pinfunction "1_1") (pintype "passive"))
      (node (ref "U$2") (pin "P$D32") (pinfunction "P$D32_P$D32") (pintype "bidirectional"))
    )
    (net (code "34") (name "Net-(S15-2)") (class "Default")
      (node (ref "S15") (pin "3") (pinfunction "2_3") (pintype "passive"))
      (node (ref "S16") (pin "3") (pinfunction "2_3") (pintype "passive"))
      (node (ref "S17") (pin "3") (pinfunction "2_3") (pintype "passive"))
      (node (ref "S18") (pin "3") (pinfunction "2_3") (pintype "passive"))
      (node (ref "S19") (pin "3") (pinfunction "2_3") (pintype "passive"))
      (node (ref "S20") (pin "3") (pinfunction "2_3") (pintype "passive"))
      (node (ref "S21") (pin "3") (pinfunction "2_3") (pintype "passive"))
      (node (ref "S22") (pin "3") (pinfunction "2_3") (pintype "passive"))
      (node (ref "S23") (pin "3") (pinfunction "2_3") (pintype "passive"))
      (node (ref "S24") (pin "3") (pinfunction "2_3") (pintype "passive"))
      (node (ref "S25") (pin "3") (pinfunction "2_3") (pintype "passive"))
      (node (ref "S26") (pin "3") (pinfunction "2_3") (pintype "passive"))
      (node (ref "S27") (pin "3") (pinfunction "2_3") (pintype "passive"))
      (node (ref "U$2") (pin "P$D34") (pinfunction "P$D34_P$D34") (pintype "bidirectional"))
    )
    (net (code "35") (name "Net-(S15-Pad1)") (class "Default")
      (node (ref "S15") (pin "1") (pinfunction "1_1") (pintype "passive"))
      (node (ref "S2") (pin "1") (pinfunction "1_1") (pintype "passive"))
      (node (ref "S28") (pin "1") (pinfunction "1_1") (pintype "passive"))
      (node (ref "S41") (pin "1") (pinfunction "1_1") (pintype "passive"))
      (node (ref "S53") (pin "1") (pinfunction "1_1") (pintype "passive"))
      (node (ref "U$2") (pin "P$D41") (pinfunction "P$D41_P$D41") (pintype "bidirectional"))
    )
    (net (code "36") (name "Net-(S16-Pad1)") (class "Default")
      (node (ref "S16") (pin "1") (pinfunction "1_1") (pintype "passive"))
      (node (ref "S29") (pin "1") (pinfunction "1_1") (pintype "passive"))
      (node (ref "S3") (pin "1") (pinfunction "1_1") (pintype "passive"))
      (node (ref "S42") (pin "1") (pinfunction "1_1") (pintype "passive"))
      (node (ref "S54") (pin "1") (pinfunction "1_1") (pintype "passive"))
      (node (ref "U$2") (pin "P$D40") (pinfunction "P$D40_P$D40") (pintype "bidirectional"))
    )
    (net (code "37") (name "Net-(S17-Pad1)") (class "Default")
      (node (ref "S17") (pin "1") (pinfunction "1_1") (pintype "passive"))
      (node (ref "S30") (pin "1") (pinfunction "1_1") (pintype "passive"))
      (node (ref "S4") (pin "1") (pinfunction "1_1") (pintype "passive"))
      (node (ref "S43") (pin "1") (pinfunction "1_1") (pintype "passive"))
      (node (ref "S55") (pin "1") (pinfunction "1_1") (pintype "passive"))
      (node (ref "U$2") (pin "P$D3") (pinfunction "P$D3_P$D3") (pintype "bidirectional"))
    )
    (net (code "38") (name "Net-(S18-Pad1)") (class "Default")
      (node (ref "S18") (pin "1") (pinfunction "1_1") (pintype "passive"))
      (node (ref "S31") (pin "1") (pinfunction "1_1") (pintype "passive"))
      (node (ref "S44") (pin "1") (pinfunction "1_1") (pintype "passive"))
      (node (ref "S5") (pin "1") (pinfunction "1_1") (pintype "passive"))
      (node (ref "S56") (pin "1") (pinfunction "1_1") (pintype "passive"))
      (node (ref "U$2") (pin "P$D4") (pinfunction "P$D4_P$D4") (pintype "bidirectional"))
    )
    (net (code "39") (name "Net-(S19-Pad1)") (class "Default")
      (node (ref "S19") (pin "1") (pinfunction "1_1") (pintype "passive"))
      (node (ref "S32") (pin "1") (pinfunction "1_1") (pintype "passive"))
      (node (ref "S45") (pin "1") (pinfunction "1_1") (pintype "passive"))
      (node (ref "S57") (pin "1") (pinfunction "1_1") (pintype "passive"))
      (node (ref "S6") (pin "1") (pinfunction "1_1") (pintype "passive"))
      (node (ref "U$2") (pin "P$D24") (pinfunction "P$D24_P$D24") (pintype "bidirectional"))
    )
    (net (code "40") (name "Net-(S20-Pad1)") (class "Default")
      (node (ref "S20") (pin "1") (pinfunction "1_1") (pintype "passive"))
      (node (ref "S33") (pin "1") (pinfunction "1_1") (pintype "passive"))
      (node (ref "S46") (pin "1") (pinfunction "1_1") (pintype "passive"))
      (node (ref "S58") (pin "1") (pinfunction "1_1") (pintype "passive"))
      (node (ref "S7") (pin "1") (pinfunction "1_1") (pintype "passive"))
      (node (ref "U$2") (pin "P$D25") (pinfunction "P$D25_P$D25") (pintype "bidirectional"))
    )
    (net (code "41") (name "Net-(S21-Pad1)") (class "Default")
      (node (ref "S21") (pin "1") (pinfunction "1_1") (pintype "passive"))
      (node (ref "S34") (pin "1") (pinfunction "1_1") (pintype "passive"))
      (node (ref "S47") (pin "1") (pinfunction "1_1") (pintype "passive"))
      (node (ref "S59") (pin "1") (pinfunction "1_1") (pintype "passive"))
      (node (ref "S8") (pin "1") (pinfunction "1_1") (pintype "passive"))
      (node (ref "U$2") (pin "P$D39") (pinfunction "P$D39_P$D39") (pintype "bidirectional"))
    )
    (net (code "42") (name "Net-(S22-Pad1)") (class "Default")
      (node (ref "S22") (pin "1") (pinfunction "1_1") (pintype "passive"))
      (node (ref "S35") (pin "1") (pinfunction "1_1") (pintype "passive"))
      (node (ref "S48") (pin "1") (pinfunction "1_1") (pintype "passive"))
      (node (ref "S60") (pin "1") (pinfunction "1_1") (pintype "passive"))
      (node (ref "S9") (pin "1") (pinfunction "1_1") (pintype "passive"))
      (node (ref "U$2") (pin "P$D23") (pinfunction "P$D23_P$D23") (pintype "bidirectional"))
    )
    (net (code "43") (name "Net-(S28-2)") (class "Default")
      (node (ref "S28") (pin "3") (pinfunction "2_3") (pintype "passive"))
      (node (ref "S29") (pin "3") (pinfunction "2_3") (pintype "passive"))
      (node (ref "S30") (pin "3") (pinfunction "2_3") (pintype "passive"))
      (node (ref "S31") (pin "3") (pinfunction "2_3") (pintype "passive"))
      (node (ref "S32") (pin "3") (pinfunction "2_3") (pintype "passive"))
      (node (ref "S33") (pin "3") (pinfunction "2_3") (pintype "passive"))
      (node (ref "S34") (pin "3") (pinfunction "2_3") (pintype "passive"))
      (node (ref "S35") (pin "3") (pinfunction "2_3") (pintype "passive"))
      (node (ref "S36") (pin "3") (pinfunction "2_3") (pintype "passive"))
      (node (ref "S37") (pin "3") (pinfunction "2_3") (pintype "passive"))
      (node (ref "S38") (pin "3") (pinfunction "2_3") (pintype "passive"))
      (node (ref "S39") (pin "3") (pinfunction "2_3") (pintype "passive"))
      (node (ref "S40") (pin "3") (pinfunction "2_3") (pintype "passive"))
      (node (ref "U$2") (pin "P$D35") (pinfunction "P$D35_P$D35") (pintype "bidirectional"))
    )
    (net (code "44") (name "Net-(S41-2)") (class "Default")
      (node (ref "S41") (pin "3") (pinfunction "2_3") (pintype "passive"))
      (node (ref "S42") (pin "3") (pinfunction "2_3") (pintype "passive"))
      (node (ref "S43") (pin "3") (pinfunction "2_3") (pintype "passive"))
      (node (ref "S44") (pin "3") (pinfunction "2_3") (pintype "passive"))
      (node (ref "S45") (pin "3") (pinfunction "2_3") (pintype "passive"))
      (node (ref "S46") (pin "3") (pinfunction "2_3") (pintype "passive"))
      (node (ref "S47") (pin "3") (pinfunction "2_3") (pintype "passive"))
      (node (ref "S48") (pin "3") (pinfunction "2_3") (pintype "passive"))
      (node (ref "S49") (pin "3") (pinfunction "2_3") (pintype "passive"))
      (node (ref "S50") (pin "3") (pinfunction "2_3") (pintype "passive"))
      (node (ref "S51") (pin "3") (pinfunction "2_3") (pintype "passive"))
      (node (ref "S52") (pin "3") (pinfunction "2_3") (pintype "passive"))
      (node (ref "U$2") (pin "P$D36") (pinfunction "P$D36_P$D36") (pintype "bidirectional"))
    )
    (net (code "45") (name "Net-(S53-2)") (class "Default")
      (node (ref "S53") (pin "3") (pinfunction "2_3") (pintype "passive"))
      (node (ref "S54") (pin "3") (pinfunction "2_3") (pintype "passive"))
      (node (ref "S55") (pin "3") (pinfunction "2_3") (pintype "passive"))
      (node (ref "S56") (pin "3") (pinfunction "2_3") (pintype "passive"))
      (node (ref "S57") (pin "3") (pinfunction "2_3") (pintype "passive"))
      (node (ref "S58") (pin "3") (pinfunction "2_3") (pintype "passive"))
      (node (ref "S59") (pin "3") (pinfunction "2_3") (pintype "passive"))
      (node (ref "S60") (pin "3") (pinfunction "2_3") (pintype "passive"))
      (node (ref "S61") (pin "3") (pinfunction "2_3") (pintype "passive"))
      (node (ref "S62") (pin "3") (pinfunction "2_3") (pintype "passive"))
      (node (ref "S63") (pin "3") (pinfunction "2_3") (pintype "passive"))
      (node (ref "U$2") (pin "P$D37") (pinfunction "P$D37_P$D37") (pintype "bidirectional"))
    )
    (net (code "46") (name "Net-(S64-S)") (class "Default")
      (node (ref "S64") (pin "3") (pinfunction "S_3") (pintype "passive"))
      (node (ref "U$4") (pin "VCC") (pinfunction "VCC_VCC") (pintype "bidirectional"))
    )
    (net (code "47") (name "Net-(S65-P)") (class "Default")
      (node (ref "J2-PWR") (pin "1") (pinfunction "1_1") (pintype "passive"))
      (node (ref "J4") (pin "1") (pinfunction "1_1") (pintype "passive"))
      (node (ref "S65") (pin "2") (pinfunction "P_2") (pintype "passive"))
    )
    (net (code "48") (name "Net-(U$1-PadLR)") (class "Default")
      (node (ref "U$1") (pin "LR") (pinfunction "LR_LR") (pintype "output"))
      (node (ref "U$2") (pin "P$D16") (pinfunction "P$D16_P$D16") (pintype "bidirectional"))
    )
    (net (code "49") (name "Net-(U$1-PadLRV+)") (class "Default")
      (node (ref "U$1") (pin "LRV+") (pinfunction "LRV+_LRV+") (pintype "power_in"))
      (node (ref "U$1") (pin "UDV+") (pinfunction "UDV+_UDV+") (pintype "power_in"))
      (node (ref "U$2") (pin "P$33V") (pinfunction "P$33V_P$33V") (pintype "bidirectional"))
      (node (ref "U$2") (pin "P$33V2") (pinfunction "P$33V_P$33V2") (pintype "bidirectional"))
      (node (ref "U$2") (pin "P$33V3") (pinfunction "P$33V_P$33V3") (pintype "bidirectional"))
    )
    (net (code "50") (name "Net-(U$1-PadUD)") (class "Default")
      (node (ref "U$1") (pin "UD") (pinfunction "UD_UD") (pintype "output"))
      (node (ref "U$2") (pin "P$D17") (pinfunction "P$D17_P$D17") (pintype "bidirectional"))
    )
    (net (code "51") (name "Net-(U$4-RXD)") (class "Default")
      (node (ref "U$2") (pin "P$D14") (pinfunction "P$D14_P$D14") (pintype "bidirectional"))
      (node (ref "U$4") (pin "RX") (pinfunction "RXD_RX") (pintype "bidirectional"))
    )
    (net (code "52") (name "Net-(U$4-TXD)") (class "Default")
      (node (ref "U$2") (pin "P$D15") (pinfunction "P$D15_P$D15") (pintype "bidirectional"))
      (node (ref "U$4") (pin "TX") (pinfunction "TXD_TX") (pintype "bidirectional"))
    )
    (net (code "53") (name "VCC") (class "Default")
      (node (ref "C1") (pin "2") (pinfunction "2_2") (pintype "passive"))
      (node (ref "IC1") (pin "3") (pinfunction "VIN_3") (pintype "bidirectional"))
      (node (ref "S65") (pin "3") (pinfunction "S_3") (pintype "passive"))
      (node (ref "U$2") (pin "P$VIN") (pinfunction "P$VIN_P$VIN") (pintype "bidirectional"))
    )
    (net (code "54") (name "unconnected-(IC1-HEATSINK-Pad4)") (class "Default")
      (node (ref "IC1") (pin "4") (pinfunction "HEATSINK_4") (pintype "bidirectional"))
    )
    (net (code "55") (name "unconnected-(J1-Pad10)") (class "Default")
      (node (ref "J1") (pin "10") (pinfunction "10_10") (pintype "passive"))
    )
    (net (code "56") (name "unconnected-(J1-Pad11)") (class "Default")
      (node (ref "J1") (pin "11") (pinfunction "11_11") (pintype "passive"))
    )
    (net (code "57") (name "unconnected-(J1-Pad12)") (class "Default")
      (node (ref "J1") (pin "12") (pinfunction "12_12") (pintype "passive"))
    )
    (net (code "58") (name "unconnected-(J1-Pad13)") (class "Default")
      (node (ref "J1") (pin "13") (pinfunction "13_13") (pintype "passive"))
    )
    (net (code "59") (name "unconnected-(J1-Pad14)") (class "Default")
      (node (ref "J1") (pin "14") (pinfunction "14_14") (pintype "passive"))
    )
    (net (code "60") (name "unconnected-(S64-O-Pad1)") (class "Default")
      (node (ref "S64") (pin "1") (pinfunction "O_1") (pintype "passive"))
    )
    (net (code "61") (name "unconnected-(S65-O-Pad1)") (class "Default")
      (node (ref "S65") (pin "1") (pinfunction "O_1") (pintype "passive"))
    )
    (net (code "62") (name "unconnected-(U$1-PadLR2)") (class "Default")
      (node (ref "U$1") (pin "LR2") (pinfunction "LR2_LR2") (pintype "output"))
    )
    (net (code "63") (name "unconnected-(U$1-PadUD2)") (class "Default")
      (node (ref "U$1") (pin "UD2") (pinfunction "UD2_UD2") (pintype "output"))
    )
    (net (code "64") (name "unconnected-(U$2-PadP$D2)") (class "Default")
      (node (ref "U$2") (pin "P$D2") (pinfunction "P$D2_P$D2") (pintype "bidirectional"))
    )
    (net (code "65") (name "unconnected-(U$2-PadP$D5)") (class "Default")
      (node (ref "U$2") (pin "P$D5") (pinfunction "P$D5_P$D5") (pintype "bidirectional"))
    )
    (net (code "66") (name "unconnected-(U$2-PadP$D6)") (class "Default")
      (node (ref "U$2") (pin "P$D6") (pinfunction "P$D6_P$D6") (pintype "bidirectional"))
    )
    (net (code "67") (name "unconnected-(U$2-PadP$D7)") (class "Default")
      (node (ref "U$2") (pin "P$D7") (pinfunction "P$D7_P$D7") (pintype "bidirectional"))
    )
    (net (code "68") (name "unconnected-(U$2-PadP$D11)") (class "Default")
      (node (ref "U$2") (pin "P$D11") (pinfunction "P$D11_P$D11") (pintype "bidirectional"))
    )
    (net (code "69") (name "unconnected-(U$2-PadP$D13)") (class "Default")
      (node (ref "U$2") (pin "P$D13") (pinfunction "P$D13_P$D13") (pintype "bidirectional"))
    )
    (net (code "70") (name "unconnected-(U$2-PadP$D22)") (class "Default")
      (node (ref "U$2") (pin "P$D22") (pinfunction "P$D22_P$D22") (pintype "bidirectional"))
    )
    (net (code "71") (name "unconnected-(U$2-PadP$D48)") (class "Default")
      (node (ref "U$2") (pin "P$D48") (pinfunction "P$D48_P$D48") (pintype "bidirectional"))
    )
    (net (code "72") (name "unconnected-(U$2-PadP$D49)") (class "Default")
      (node (ref "U$2") (pin "P$D49") (pinfunction "P$D49_P$D49") (pintype "bidirectional"))
    )
    (net (code "73") (name "unconnected-(U$2-PadP$D50)") (class "Default")
      (node (ref "U$2") (pin "P$D50") (pinfunction "P$D50_P$D50") (pintype "bidirectional"))
    )
    (net (code "74") (name "unconnected-(U$2-PadP$D51)") (class "Default")
      (node (ref "U$2") (pin "P$D51") (pinfunction "P$D51_P$D51") (pintype "bidirectional"))
    )
    (net (code "75") (name "unconnected-(U$2-PadP$D52)") (class "Default")
      (node (ref "U$2") (pin "P$D52") (pinfunction "P$D52_P$D52") (pintype "bidirectional"))
    )
    (net (code "76") (name "unconnected-(U$2-PadP$D53)") (class "Default")
      (node (ref "U$2") (pin "P$D53") (pinfunction "P$D53_P$D53") (pintype "bidirectional"))
    )
    (net (code "77") (name "unconnected-(U$2-PadP$D54)") (class "Default")
      (node (ref "U$2") (pin "P$D54") (pinfunction "P$D54_P$D54") (pintype "bidirectional"))
    )
    (net (code "78") (name "unconnected-(U$2-PadP$LED)") (class "Default")
      (node (ref "U$2") (pin "P$LED") (pinfunction "P$LED_P$LED") (pintype "bidirectional"))
    )
    (net (code "79") (name "unconnected-(U$2-PadP$PGM)") (class "Default")
      (node (ref "U$2") (pin "P$PGM") (pinfunction "P$PGM_P$PGM") (pintype "bidirectional"))
    )
    (net (code "80") (name "unconnected-(U$2-PadP$R+)") (class "Default")
      (node (ref "U$2") (pin "P$R+") (pinfunction "P$R+_P$R+") (pintype "bidirectional"))
    )
    (net (code "81") (name "unconnected-(U$2-PadP$R-)") (class "Default")
      (node (ref "U$2") (pin "P$R-") (pinfunction "P$R-_P$R-") (pintype "bidirectional"))
    )
    (net (code "82") (name "unconnected-(U$2-PadP$RST)") (class "Default")
      (node (ref "U$2") (pin "P$RST") (pinfunction "P$RST_P$RST") (pintype "bidirectional"))
    )
    (net (code "83") (name "unconnected-(U$2-PadP$T+)") (class "Default")
      (node (ref "U$2") (pin "P$T+") (pinfunction "P$T+_P$T+") (pintype "bidirectional"))
    )
    (net (code "84") (name "unconnected-(U$2-PadP$T-)") (class "Default")
      (node (ref "U$2") (pin "P$T-") (pinfunction "P$T-_P$T-") (pintype "bidirectional"))
    )
    (net (code "85") (name "unconnected-(U$2-PadP$VUSB)") (class "Default")
      (node (ref "U$2") (pin "P$VUSB") (pinfunction "P$VUSB_P$VUSB") (pintype "bidirectional"))
    )
    (net (code "86") (name "unconnected-(U$4-PadGPIO2)") (class "Default")
      (node (ref "U$4") (pin "GPIO2") (pinfunction "GPIO2_GPIO2") (pintype "bidirectional"))
    )
  )
)
